# DISCHARGE.net
KiCad netlist of a schematic drawn in EAGLE
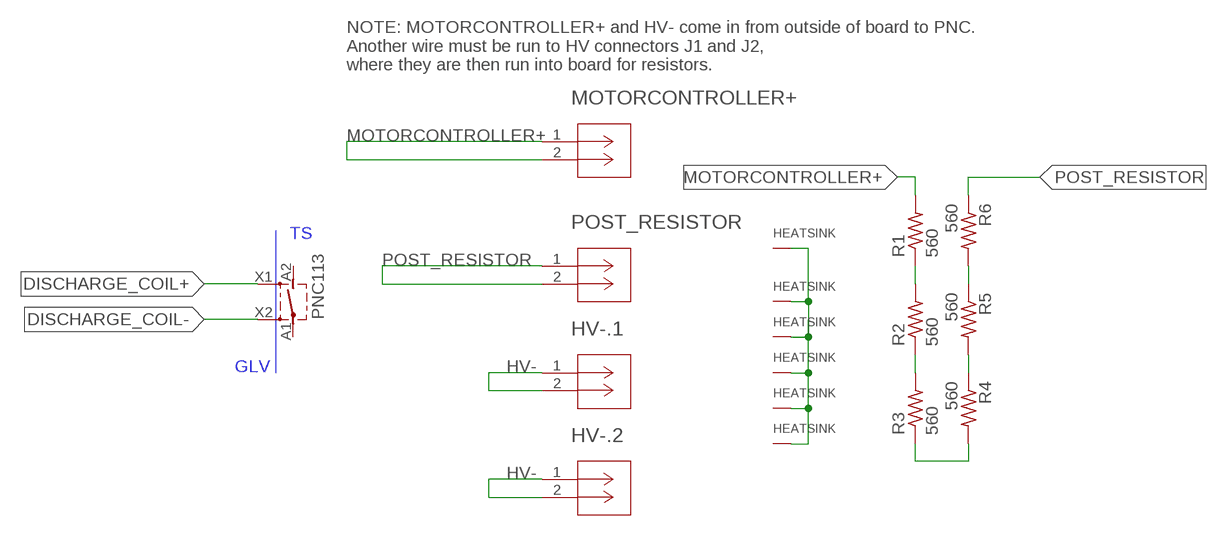
[diagram p0: schematic, sheet 1]

(export (version "E")
  (design (tool "Eeschema 10.0.6"))
  (components
    (comp (ref "HV-.1")
      (value "770966-1")
      (footprint "eagle-import:CONN2_770966-1")
      (fields (field (name "MANUFACTURER_PART_NUMBER") "7709661"))
      (libsource (lib "eagle-import") (part "770966-1"))
    )
    (comp (ref "HV-.2")
      (value "770966-1")
      (footprint "eagle-import:CONN2_770966-1")
      (fields (field (name "MANUFACTURER_PART_NUMBER") "7709661"))
      (libsource (lib "eagle-import") (part "770966-1"))
    )
    (comp (ref "MOTORCONTROLLER+")
      (value "770966-1")
      (footprint "eagle-import:CONN2_770966-1")
      (fields (field (name "MANUFACTURER_PART_NUMBER") "7709661"))
      (libsource (lib "eagle-import") (part "770966-1"))
    )
    (comp (ref "PNC113")
      (value "PNC113")
      (footprint "eagle-import:PNC113")
      (libsource (lib "eagle-import") (part "PNC113"))
    )
    (comp (ref "POST_RESISTOR")
      (value "770966-1")
      (footprint "eagle-import:CONN2_770966-1")
      (fields (field (name "MANUFACTURER_PART_NUMBER") "7709661"))
      (libsource (lib "eagle-import") (part "770966-1"))
    )
    (comp (ref "R1")
      (value "560")
      (footprint "eagle-import:TO126")
      (libsource (lib "eagle-import") (part "PF1262-HEATSINKTO126"))
    )
    (comp (ref "R2")
      (value "560")
      (footprint "eagle-import:TO126")
      (libsource (lib "eagle-import") (part "PF1262-HEATSINKTO126"))
    )
    (comp (ref "R3")
      (value "560")
      (footprint "eagle-import:TO126")
      (libsource (lib "eagle-import") (part "PF1262-HEATSINKTO126"))
    )
    (comp (ref "R4")
      (value "560")
      (footprint "eagle-import:TO126")
      (libsource (lib "eagle-import") (part "PF1262-HEATSINKTO126"))
    )
    (comp (ref "R5")
      (value "560")
      (footprint "eagle-import:TO126")
      (libsource (lib "eagle-import") (part "PF1262-HEATSINKTO126"))
    )
    (comp (ref "R6")
      (value "560")
      (footprint "eagle-import:TO126")
      (libsource (lib "eagle-import") (part "PF1262-HEATSINKTO126"))
    )
  )
  (nets
    (net (code "1") (name "/HV-") (class "Default")
      (node (ref "HV-.1") (pin "1") (pinfunction "1_1") (pintype "passive"))
      (node (ref "HV-.1") (pin "2") (pinfunction "2_2") (pintype "passive"))
      (node (ref "HV-.2") (pin "1") (pinfunction "1_1") (pintype "passive"))
      (node (ref "HV-.2") (pin "2") (pinfunction "2_2") (pintype "passive"))
    )
    (net (code "2") (name "DISCHARGE_COIL+") (class "Default")
      (node (ref "PNC113") (pin "X1") (pinfunction "X1_X1") (pintype "passive"))
    )
    (net (code "3") (name "DISCHARGE_COIL-") (class "Default")
      (node (ref "PNC113") (pin "X2") (pinfunction "X2_X2") (pintype "passive"))
    )
    (net (code "4") (name "MOTORCONTROLLER+") (class "Default")
      (node (ref "MOTORCONTROLLER+") (pin "1") (pinfunction "1_1") (pintype "passive"))
      (node (ref "MOTORCONTROLLER+") (pin "2") (pinfunction "2_2") (pintype "passive"))
      (node (ref "R1") (pin "2") (pinfunction "2_2") (pintype "passive"))
    )
    (net (code "5") (name "Net-(R1-Pad1)") (class "Default")
      (node (ref "R1") (pin "1") (pinfunction "1_1") (pintype "passive"))
      (node (ref "R2") (pin "2") (pinfunction "2_2") (pintype "passive"))
    )
    (net (code "6") (name "Net-(R1A-1)") (class "Default")
      (node (ref "R1") (pin "THERM") (pinfunction "1_THERM") (pintype "passive"))
      (node (ref "R2") (pin "THERM") (pinfunction "1_THERM") (pintype "passive"))
      (node (ref "R3") (pin "THERM") (pinfunction "1_THERM") (pintype "passive"))
      (node (ref "R4") (pin "THERM") (pinfunction "1_THERM") (pintype "passive"))
      (node (ref "R5") (pin "THERM") (pinfunction "1_THERM") (pintype "passive"))
      (node (ref "R6") (pin "THERM") (pinfunction "1_THERM") (pintype "passive"))
    )
    (net (code "7") (name "Net-(R2-Pad1)") (class "Default")
      (node (ref "R2") (pin "1") (pinfunction "1_1") (pintype "passive"))
      (node (ref "R3") (pin "2") (pinfunction "2_2") (pintype "passive"))
    )
    (net (code "8") (name "Net-(R3-Pad1)") (class "Default")
      (node (ref "R3") (pin "1") (pinfunction "1_1") (pintype "passive"))
      (node (ref "R4") (pin "2") (pinfunction "2_2") (pintype "passive"))
    )
    (net (code "9") (name "Net-(R4-Pad1)") (class "Default")
      (node (ref "R4") (pin "1") (pinfunction "1_1") (pintype "passive"))
      (node (ref "R5") (pin "2") (pinfunction "2_2") (pintype "passive"))
    )
    (net (code "10") (name "Net-(R5-Pad1)") (class "Default")
      (node (ref "R5") (pin "1") (pinfunction "1_1") (pintype "passive"))
      (node (ref "R6") (pin "2") (pinfunction "2_2") (pintype "passive"))
    )
    (net (code "11") (name "POST_RESISTOR") (class "Default")
      (node (ref "POST_RESISTOR") (pin "1") (pinfunction "1_1") (pintype "passive"))
      (node (ref "POST_RESISTOR") (pin "2") (pinfunction "2_2") (pintype "passive"))
      (node (ref "R6") (pin "1") (pinfunction "1_1") (pintype "passive"))
    )
    (net (code "12") (name "unconnected-(PNC113-PadA1)") (class "Default")
      (node (ref "PNC113") (pin "A1") (pinfunction "A1_A1") (pintype "passive"))
    )
    (net (code "13") (name "unconnected-(PNC113-PadA2)") (class "Default")
      (node (ref "PNC113") (pin "A2") (pinfunction "A2_A2") (pintype "passive"))
    )
  )
)
